# MySens-easyESP32b-007c.net
KiCad netlist of a schematic drawn in EAGLE
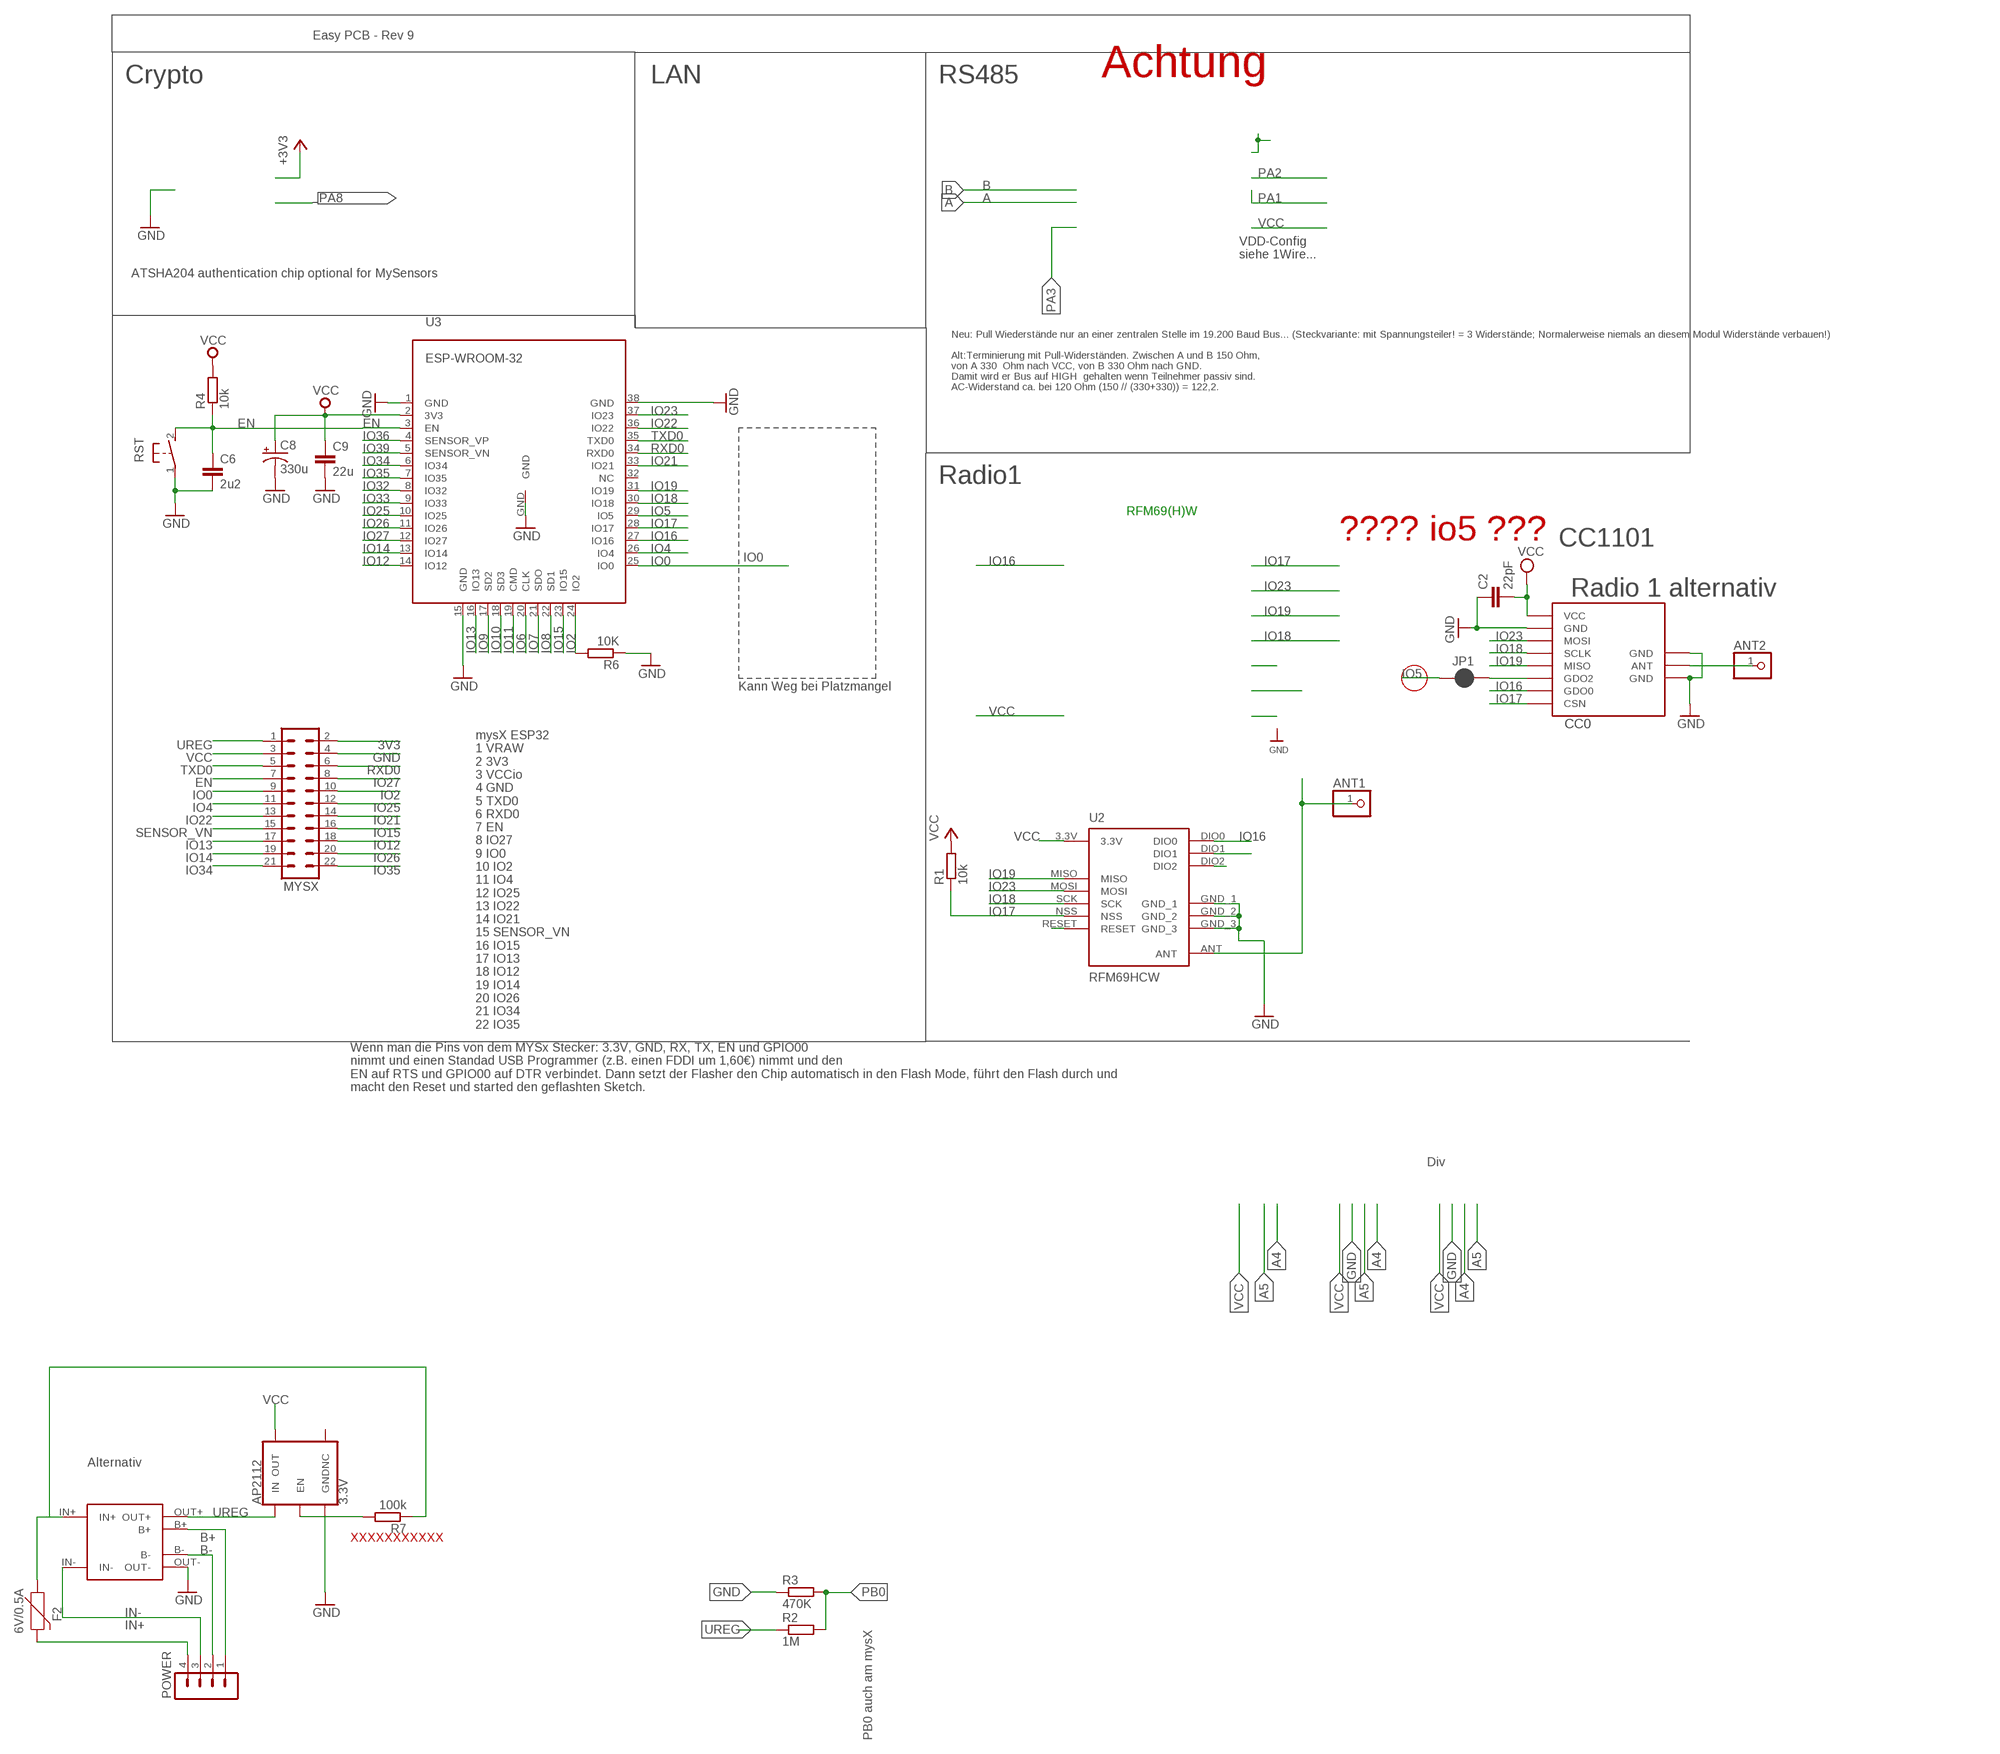
[diagram p0: schematic, sheet 1]

(export (version "E")
  (design (tool "Eeschema 10.0.6"))
  (components
    (comp (ref "ANT1")
      (value "PINHD-1X1")
      (footprint "eagle-import:1X01")
      (libsource (lib "eagle-import") (part "PINHD-1X1"))
    )
    (comp (ref "ANT2")
      (value "PINHD-1X1")
      (footprint "eagle-import:1X01")
      (libsource (lib "eagle-import") (part "PINHD-1X1"))
    )
    (comp (ref "AP2112")
      (value "3.3V")
      (footprint "eagle-import:SOT23-5")
      (libsource (lib "eagle-import") (part "V_REG_AP2112K-3.3V"))
    )
    (comp (ref "C2")
      (value "22pF")
      (footprint "eagle-import:C0805")
      (libsource (lib "eagle-import") (part "C-EUC0805"))
    )
    (comp (ref "C6")
      (value "2u2")
      (footprint "eagle-import:C0805")
      (libsource (lib "eagle-import") (part "rcl@1_C-EUC0805"))
    )
    (comp (ref "C8")
      (value "330u")
      (footprint "eagle-import:VISHAY_C")
      (libsource (lib "eagle-import") (part "CAP_POLSMD"))
    )
    (comp (ref "C9")
      (value "22u")
      (footprint "eagle-import:C0805")
      (libsource (lib "eagle-import") (part "rcl@1_C-EUC0805"))
    )
    (comp (ref "CC0")
      (value "CC1101")
      (footprint "eagle-import:CC1101_MODULE1_SMD")
      (libsource (lib "eagle-import") (part "CC1101_MODULE1SMD"))
    )
    (comp (ref "F2")
      (value "6V/0.5A")
      (footprint "eagle-import:1206")
      (libsource (lib "eagle-import") (part "PPTC_HALF-AMP"))
    )
    (comp (ref "JP1")
      (value "JUMPER-SMT_2_NC_PASTE_NO-SILK")
      (footprint "eagle-import:SMT-JUMPER_2_NC_PASTE_NO-SILK")
      (libsource (lib "eagle-import") (part "JUMPER-SMT_2_NC_PASTE_NO-SILK"))
    )
    (comp (ref "MYSX")
      (value "MA11-2")
      (footprint "eagle-import:MA11-2")
      (libsource (lib "eagle-import") (part "MA11-2"))
    )
    (comp (ref "POWER")
      (value "MA04-1")
      (footprint "eagle-import:MA04-1")
      (libsource (lib "eagle-import") (part "MA04-1"))
    )
    (comp (ref "R1")
      (value "10k")
      (footprint "eagle-import:M0805")
      (libsource (lib "eagle-import") (part "R-EU_M0805"))
    )
    (comp (ref "R2")
      (value "1M")
      (footprint "eagle-import:M0805")
      (libsource (lib "eagle-import") (part "R-EU_M0805"))
    )
    (comp (ref "R3")
      (value "470K")
      (footprint "eagle-import:M0805")
      (libsource (lib "eagle-import") (part "R-EU_M0805"))
    )
    (comp (ref "R4")
      (value "10k")
      (footprint "eagle-import:M0805")
      (libsource (lib "eagle-import") (part "rcl@1_R-EU_M0805"))
    )
    (comp (ref "R6")
      (value "10K")
      (footprint "eagle-import:M0805")
      (libsource (lib "eagle-import") (part "R-EU_M0805"))
    )
    (comp (ref "R7")
      (value "100k")
      (footprint "eagle-import:M0805")
      (libsource (lib "eagle-import") (part "R-EU_M0805"))
    )
    (comp (ref "RST")
      (value "DTSM-3")
      (footprint "eagle-import:DTSM-3")
      (libsource (lib "eagle-import") (part "DTSM-3"))
    )
    (comp (ref "TP4056")
      (value "TP4056-MODULE")
      (footprint "eagle-import:TP4056-LITHIUM-PROTECTED-MODULE")
      (libsource (lib "eagle-import") (part "TP4056-MODULE"))
    )
    (comp (ref "U2")
      (value "RFM69HCW")
      (footprint "eagle-import:RFM69HCW-XXXS2")
      (libsource (lib "eagle-import") (part "RFM69HCW"))
    )
    (comp (ref "U3")
      (value "ESP-WROOM-32")
      (footprint "eagle-import:ESP-WROOM-32")
      (libsource (lib "eagle-import") (part "ESP-WROOM-32"))
    )
  )
  (nets
    (net (code "2") (name "/3V3") (class "Default")
      (node (ref "MYSX") (pin "2") (pinfunction "2_2") (pintype "passive"))
    )
    (net (code "3") (name "/B+") (class "Default")
      (node (ref "POWER") (pin "1") (pinfunction "1_1") (pintype "passive"))
      (node (ref "TP4056") (pin "B+") (pinfunction "B+_B+") (pintype "power_in"))
    )
    (net (code "4") (name "/B-") (class "Default")
      (node (ref "POWER") (pin "2") (pinfunction "2_2") (pintype "passive"))
      (node (ref "TP4056") (pin "B-") (pinfunction "B-_B-") (pintype "power_in"))
    )
    (net (code "5") (name "/EN") (class "Default")
      (node (ref "C6") (pin "1") (pinfunction "1_1") (pintype "passive"))
      (node (ref "MYSX") (pin "7") (pinfunction "7_7") (pintype "passive"))
      (node (ref "R4") (pin "1") (pinfunction "1_1") (pintype "passive"))
      (node (ref "RST") (pin "2") (pinfunction "2_2") (pintype "passive"))
      (node (ref "U3") (pin "3") (pinfunction "EN_3") (pintype "bidirectional"))
    )
    (net (code "6") (name "/IN+") (class "Default")
      (node (ref "F2") (pin "2") (pinfunction "2_2") (pintype "bidirectional"))
      (node (ref "POWER") (pin "4") (pinfunction "4_4") (pintype "passive"))
    )
    (net (code "7") (name "/IN-") (class "Default")
      (node (ref "POWER") (pin "3") (pinfunction "3_3") (pintype "passive"))
      (node (ref "TP4056") (pin "IN-") (pinfunction "IN-_IN-") (pintype "power_in"))
    )
    (net (code "8") (name "/IO0") (class "Default")
      (node (ref "MYSX") (pin "9") (pinfunction "9_9") (pintype "passive"))
      (node (ref "U3") (pin "25") (pinfunction "IO0_25") (pintype "bidirectional"))
    )
    (net (code "9") (name "/IO2") (class "Default")
      (node (ref "MYSX") (pin "10") (pinfunction "10_10") (pintype "passive"))
      (node (ref "R6") (pin "2") (pinfunction "2_2") (pintype "passive"))
      (node (ref "U3") (pin "24") (pinfunction "IO2_24") (pintype "bidirectional"))
    )
    (net (code "10") (name "/IO4") (class "Default")
      (node (ref "MYSX") (pin "11") (pinfunction "11_11") (pintype "passive"))
      (node (ref "U3") (pin "26") (pinfunction "IO4_26") (pintype "bidirectional"))
    )
    (net (code "11") (name "/IO5") (class "Default")
      (node (ref "JP1") (pin "1") (pinfunction "1_1") (pintype "passive"))
      (node (ref "U3") (pin "29") (pinfunction "IO5_29") (pintype "bidirectional"))
    )
    (net (code "12") (name "/IO6") (class "Default")
      (node (ref "U3") (pin "20") (pinfunction "CLK_20") (pintype "bidirectional"))
    )
    (net (code "13") (name "/IO7") (class "Default")
      (node (ref "U3") (pin "21") (pinfunction "SDO_21") (pintype "bidirectional"))
    )
    (net (code "14") (name "/IO8") (class "Default")
      (node (ref "U3") (pin "22") (pinfunction "SD1_22") (pintype "bidirectional"))
    )
    (net (code "15") (name "/IO9") (class "Default")
      (node (ref "U3") (pin "17") (pinfunction "SD2_17") (pintype "bidirectional"))
    )
    (net (code "16") (name "/IO10") (class "Default")
      (node (ref "U3") (pin "18") (pinfunction "SD3_18") (pintype "bidirectional"))
    )
    (net (code "17") (name "/IO11") (class "Default")
      (node (ref "U3") (pin "19") (pinfunction "CMD_19") (pintype "bidirectional"))
    )
    (net (code "18") (name "/IO12") (class "Default")
      (node (ref "MYSX") (pin "18") (pinfunction "18_18") (pintype "passive"))
      (node (ref "U3") (pin "14") (pinfunction "IO12_14") (pintype "bidirectional"))
    )
    (net (code "19") (name "/IO13") (class "Default")
      (node (ref "MYSX") (pin "17") (pinfunction "17_17") (pintype "passive"))
      (node (ref "U3") (pin "16") (pinfunction "IO13_16") (pintype "bidirectional"))
    )
    (net (code "20") (name "/IO14") (class "Default")
      (node (ref "MYSX") (pin "19") (pinfunction "19_19") (pintype "passive"))
      (node (ref "U3") (pin "13") (pinfunction "IO14_13") (pintype "bidirectional"))
    )
    (net (code "21") (name "/IO15") (class "Default")
      (node (ref "MYSX") (pin "16") (pinfunction "16_16") (pintype "passive"))
      (node (ref "U3") (pin "23") (pinfunction "IO15_23") (pintype "bidirectional"))
    )
    (net (code "22") (name "/IO16") (class "Default")
      (node (ref "CC0") (pin "GDO0") (pinfunction "GDO0_GDO0") (pintype "bidirectional"))
      (node (ref "U2") (pin "DIO0") (pinfunction "DIO0_DIO0") (pintype "bidirectional"))
      (node (ref "U3") (pin "27") (pinfunction "IO16_27") (pintype "bidirectional"))
    )
    (net (code "23") (name "/IO17") (class "Default")
      (node (ref "CC0") (pin "CSN") (pinfunction "CSN_CSN") (pintype "bidirectional"))
      (node (ref "R1") (pin "1") (pinfunction "1_1") (pintype "passive"))
      (node (ref "U2") (pin "NSS") (pinfunction "NSS_NSS") (pintype "input"))
      (node (ref "U3") (pin "28") (pinfunction "IO17_28") (pintype "bidirectional"))
    )
    (net (code "24") (name "/IO18") (class "Default")
      (node (ref "CC0") (pin "SCLK") (pinfunction "SCLK_SCLK") (pintype "bidirectional"))
      (node (ref "U2") (pin "SCK") (pinfunction "SCK_SCK") (pintype "input"))
      (node (ref "U3") (pin "30") (pinfunction "IO18_30") (pintype "bidirectional"))
    )
    (net (code "25") (name "/IO19") (class "Default")
      (node (ref "CC0") (pin "MISO") (pinfunction "MISO_MISO") (pintype "bidirectional"))
      (node (ref "U2") (pin "MISO") (pinfunction "MISO_MISO") (pintype "bidirectional"))
      (node (ref "U3") (pin "31") (pinfunction "IO19_31") (pintype "bidirectional"))
    )
    (net (code "26") (name "/IO21") (class "Default")
      (node (ref "MYSX") (pin "14") (pinfunction "14_14") (pintype "passive"))
      (node (ref "U3") (pin "33") (pinfunction "IO21_33") (pintype "bidirectional"))
    )
    (net (code "27") (name "/IO22") (class "Default")
      (node (ref "MYSX") (pin "13") (pinfunction "13_13") (pintype "passive"))
      (node (ref "U3") (pin "36") (pinfunction "IO22_36") (pintype "bidirectional"))
    )
    (net (code "28") (name "/IO23") (class "Default")
      (node (ref "CC0") (pin "MOSI") (pinfunction "MOSI_MOSI") (pintype "bidirectional"))
      (node (ref "U2") (pin "MOSI") (pinfunction "MOSI_MOSI") (pintype "input"))
      (node (ref "U3") (pin "37") (pinfunction "IO23_37") (pintype "bidirectional"))
    )
    (net (code "29") (name "/IO25") (class "Default")
      (node (ref "MYSX") (pin "12") (pinfunction "12_12") (pintype "passive"))
      (node (ref "U3") (pin "10") (pinfunction "IO25_10") (pintype "bidirectional"))
    )
    (net (code "30") (name "/IO26") (class "Default")
      (node (ref "MYSX") (pin "20") (pinfunction "20_20") (pintype "passive"))
      (node (ref "U3") (pin "11") (pinfunction "IO26_11") (pintype "bidirectional"))
    )
    (net (code "31") (name "/IO27") (class "Default")
      (node (ref "MYSX") (pin "8") (pinfunction "8_8") (pintype "passive"))
      (node (ref "U3") (pin "12") (pinfunction "IO27_12") (pintype "bidirectional"))
    )
    (net (code "32") (name "/IO32") (class "Default")
      (node (ref "U3") (pin "8") (pinfunction "IO32_8") (pintype "bidirectional"))
    )
    (net (code "33") (name "/IO33") (class "Default")
      (node (ref "U3") (pin "9") (pinfunction "IO33_9") (pintype "bidirectional"))
    )
    (net (code "34") (name "/IO34") (class "Default")
      (node (ref "MYSX") (pin "21") (pinfunction "21_21") (pintype "passive"))
      (node (ref "U3") (pin "6") (pinfunction "IO34_6") (pintype "bidirectional"))
    )
    (net (code "35") (name "/IO35") (class "Default")
      (node (ref "MYSX") (pin "22") (pinfunction "22_22") (pintype "passive"))
      (node (ref "U3") (pin "7") (pinfunction "IO35_7") (pintype "bidirectional"))
    )
    (net (code "36") (name "/IO36") (class "Default")
      (node (ref "U3") (pin "4") (pinfunction "SENSOR_VP_4") (pintype "bidirectional"))
    )
    (net (code "37") (name "/IO39") (class "Default")
      (node (ref "U3") (pin "5") (pinfunction "SENSOR_VN_5") (pintype "bidirectional"))
    )
    (net (code "41") (name "/RXD0") (class "Default")
      (node (ref "MYSX") (pin "6") (pinfunction "6_6") (pintype "passive"))
      (node (ref "U3") (pin "34") (pinfunction "RXD0_34") (pintype "bidirectional"))
    )
    (net (code "42") (name "/SENSOR_VN") (class "Default")
      (node (ref "MYSX") (pin "15") (pinfunction "15_15") (pintype "passive"))
    )
    (net (code "43") (name "/TXD0") (class "Default")
      (node (ref "MYSX") (pin "5") (pinfunction "5_5") (pintype "passive"))
      (node (ref "U3") (pin "35") (pinfunction "TXD0_35") (pintype "bidirectional"))
    )
    (net (code "48") (name "GND") (class "Default")
      (node (ref "AP2112") (pin "2") (pinfunction "GND_2") (pintype "input"))
      (node (ref "C2") (pin "1") (pinfunction "1_1") (pintype "passive"))
      (node (ref "C6") (pin "2") (pinfunction "2_2") (pintype "passive"))
      (node (ref "C8") (pin "-") (pinfunction "-_-") (pintype "passive"))
      (node (ref "C9") (pin "2") (pinfunction "2_2") (pintype "passive"))
      (node (ref "CC0") (pin "GND@0") (pinfunction "GND_GND@0") (pintype "power_in"))
      (node (ref "CC0") (pin "GND@1") (pinfunction "GND_GND@1") (pintype "power_in"))
      (node (ref "CC0") (pin "GND@2") (pinfunction "GND_GND@2") (pintype "power_in"))
      (node (ref "MYSX") (pin "4") (pinfunction "4_4") (pintype "passive"))
      (node (ref "R3") (pin "1") (pinfunction "1_1") (pintype "passive"))
      (node (ref "R6") (pin "1") (pinfunction "1_1") (pintype "passive"))
      (node (ref "RST") (pin "1") (pinfunction "1_1") (pintype "passive"))
      (node (ref "TP4056") (pin "OUT-") (pinfunction "OUT-_OUT-") (pintype "power_in"))
      (node (ref "U2") (pin "GND_1") (pinfunction "GND_1_GND_1") (pintype "power_in"))
      (node (ref "U2") (pin "GND_2") (pinfunction "GND_2_GND_2") (pintype "power_in"))
      (node (ref "U2") (pin "GND_3") (pinfunction "GND_3_GND_3") (pintype "power_in"))
      (node (ref "U3") (pin "1") (pinfunction "GND_1") (pintype "bidirectional"))
      (node (ref "U3") (pin "15") (pinfunction "GND_15") (pintype "bidirectional"))
      (node (ref "U3") (pin "38") (pinfunction "GND_38") (pintype "bidirectional"))
      (node (ref "U3") (pin "GND") (pinfunction "GND_GND") (pintype "bidirectional"))
    )
    (net (code "49") (name "Net-(ANT1-Pad1)") (class "Default")
      (node (ref "ANT1") (pin "1") (pinfunction "1_1") (pintype "passive"))
      (node (ref "U2") (pin "ANT") (pinfunction "ANT_ANT") (pintype "passive"))
    )
    (net (code "50") (name "Net-(ANT2-Pad1)") (class "Default")
      (node (ref "ANT2") (pin "1") (pinfunction "1_1") (pintype "passive"))
      (node (ref "CC0") (pin "ANT") (pinfunction "ANT_ANT") (pintype "output"))
    )
    (net (code "51") (name "Net-(AP2112-EN)") (class "Default")
      (node (ref "AP2112") (pin "3") (pinfunction "EN_3") (pintype "input"))
      (node (ref "R7") (pin "2") (pinfunction "2_2") (pintype "passive"))
    )
    (net (code "52") (name "Net-(CC0-PadGDO2)") (class "Default")
      (node (ref "CC0") (pin "GDO2") (pinfunction "GDO2_GDO2") (pintype "bidirectional"))
      (node (ref "JP1") (pin "2") (pinfunction "2_2") (pintype "passive"))
    )
    (net (code "53") (name "Net-(F2-Pad1)") (class "Default")
      (node (ref "F2") (pin "1") (pinfunction "1_1") (pintype "bidirectional"))
      (node (ref "R7") (pin "1") (pinfunction "1_1") (pintype "passive"))
      (node (ref "TP4056") (pin "IN+") (pinfunction "IN+_IN+") (pintype "power_in"))
    )
    (net (code "55") (name "PB0") (class "Default")
      (node (ref "R2") (pin "2") (pinfunction "2_2") (pintype "passive"))
      (node (ref "R3") (pin "2") (pinfunction "2_2") (pintype "passive"))
    )
    (net (code "56") (name "UREG") (class "Default")
      (node (ref "AP2112") (pin "1") (pinfunction "IN_1") (pintype "input"))
      (node (ref "MYSX") (pin "1") (pinfunction "1_1") (pintype "passive"))
      (node (ref "R2") (pin "1") (pinfunction "1_1") (pintype "passive"))
      (node (ref "TP4056") (pin "OUT+") (pinfunction "OUT+_OUT+") (pintype "power_in"))
    )
    (net (code "57") (name "VCC") (class "Default")
      (node (ref "AP2112") (pin "5") (pinfunction "OUT_5") (pintype "passive"))
      (node (ref "C2") (pin "2") (pinfunction "2_2") (pintype "passive"))
      (node (ref "C8") (pin "+") (pinfunction "+_+") (pintype "passive"))
      (node (ref "C9") (pin "1") (pinfunction "1_1") (pintype "passive"))
      (node (ref "CC0") (pin "VCC") (pinfunction "VCC_VCC") (pintype "power_in"))
      (node (ref "MYSX") (pin "3") (pinfunction "3_3") (pintype "passive"))
      (node (ref "R1") (pin "2") (pinfunction "2_2") (pintype "passive"))
      (node (ref "R4") (pin "2") (pinfunction "2_2") (pintype "passive"))
      (node (ref "U2") (pin "3.3V") (pinfunction "3.3V_3.3V") (pintype "power_in"))
      (node (ref "U3") (pin "2") (pinfunction "3V3_2") (pintype "bidirectional"))
    )
    (net (code "58") (name "unconnected-(AP2112-NC-Pad4)") (class "Default")
      (node (ref "AP2112") (pin "4") (pinfunction "NC_4") (pintype "no_connect"))
    )
    (net (code "59") (name "unconnected-(U2-PadDIO1)") (class "Default")
      (node (ref "U2") (pin "DIO1") (pinfunction "DIO1_DIO1") (pintype "bidirectional"))
    )
    (net (code "60") (name "unconnected-(U2-PadDIO2)") (class "Default")
      (node (ref "U2") (pin "DIO2") (pinfunction "DIO2_DIO2") (pintype "bidirectional"))
    )
    (net (code "61") (name "unconnected-(U2-PadRESET)") (class "Default")
      (node (ref "U2") (pin "RESET") (pinfunction "RESET_RESET") (pintype "input"))
    )
    (net (code "62") (name "unconnected-(U3-NC-Pad32)") (class "Default")
      (node (ref "U3") (pin "32") (pinfunction "NC_32") (pintype "bidirectional"))
    )
  )
)
